# Adafruit_MIDI_FeatherWing.net
KiCad netlist of a schematic drawn in EAGLE
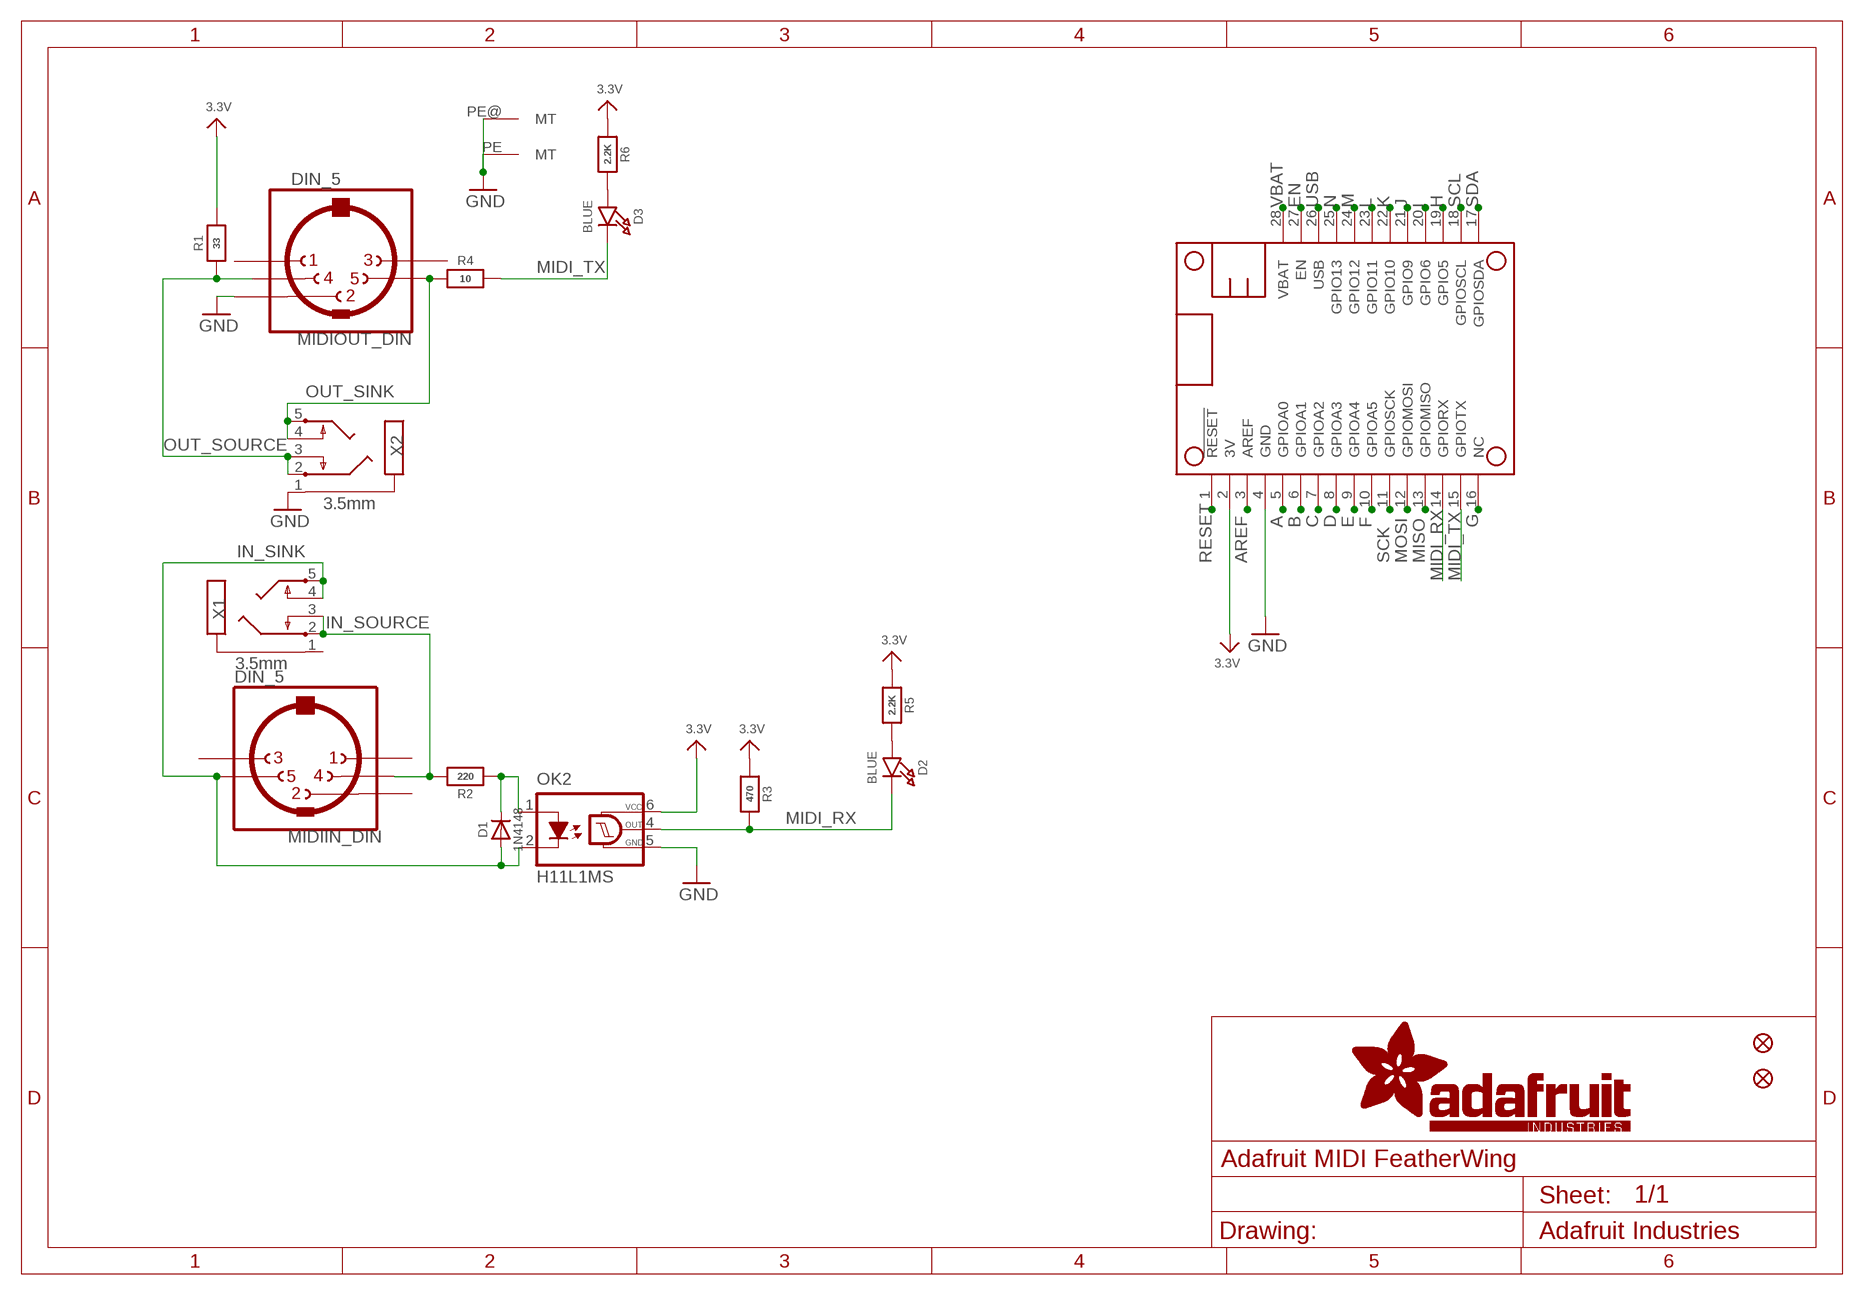
[diagram p0: schematic, sheet 1]

(export (version "E")
  (design (tool "Eeschema 10.0.6"))
  (components
    (comp (ref "D1")
      (value "1N4148")
      (footprint "eagle-import:SOD-323")
      (libsource (lib "eagle-import") (part "DIODESOD-323"))
    )
    (comp (ref "D2")
      (value "BLUE")
      (footprint "eagle-import:CHIPLED_0603")
      (libsource (lib "eagle-import") (part "LED0603"))
    )
    (comp (ref "D3")
      (value "BLUE")
      (footprint "eagle-import:CHIPLED_0603")
      (libsource (lib "eagle-import") (part "LED0603"))
    )
    (comp (ref "FID1")
      (value "FIDUCIAL_1MM")
      (footprint "eagle-import:FIDUCIAL_1MM")
      (libsource (lib "eagle-import") (part "FIDUCIAL_1MM"))
    )
    (comp (ref "FID2")
      (value "FIDUCIAL_1MM")
      (footprint "eagle-import:FIDUCIAL_1MM")
      (libsource (lib "eagle-import") (part "FIDUCIAL_1MM"))
    )
    (comp (ref "MIDIIN")
      (value "DIN_5")
      (footprint "eagle-import:CP-2350")
      (libsource (lib "eagle-import") (part "DIN_5"))
    )
    (comp (ref "MIDIOUT")
      (value "DIN_5")
      (footprint "eagle-import:CP-2350")
      (libsource (lib "eagle-import") (part "DIN_5"))
    )
    (comp (ref "MS1")
      (value "FEATHERWING_NODIM")
      (footprint "eagle-import:FEATHERWING_NODIM")
      (libsource (lib "eagle-import") (part "FEATHERWING_NODIM"))
    )
    (comp (ref "OK2")
      (value "H11L1MS")
      (footprint "eagle-import:DIL6-SMD")
      (libsource (lib "eagle-import") (part "H11LMS1"))
    )
    (comp (ref "R1")
      (value "33")
      (footprint "eagle-import:0603-NO")
      (libsource (lib "eagle-import") (part "RESISTOR_0603_NOOUT"))
    )
    (comp (ref "R2")
      (value "220")
      (footprint "eagle-import:0603-NO")
      (libsource (lib "eagle-import") (part "RESISTOR_0603_NOOUT"))
    )
    (comp (ref "R3")
      (value "470")
      (footprint "eagle-import:0603-NO")
      (libsource (lib "eagle-import") (part "RESISTOR_0603_NOOUT"))
    )
    (comp (ref "R4")
      (value "10")
      (footprint "eagle-import:0603-NO")
      (libsource (lib "eagle-import") (part "RESISTOR_0603_NOOUT"))
    )
    (comp (ref "R5")
      (value "2.2K")
      (footprint "eagle-import:0603-NO")
      (libsource (lib "eagle-import") (part "RESISTOR_0603_NOOUT"))
    )
    (comp (ref "R6")
      (value "2.2K")
      (footprint "eagle-import:0603-NO")
      (libsource (lib "eagle-import") (part "RESISTOR_0603_NOOUT"))
    )
    (comp (ref "X1")
      (value "3.5mm")
      (footprint "eagle-import:STX3100")
      (libsource (lib "eagle-import") (part "AUDIO_STEREOJACK"))
    )
    (comp (ref "X2")
      (value "3.5mm")
      (footprint "eagle-import:STX3100")
      (libsource (lib "eagle-import") (part "AUDIO_STEREOJACK"))
    )
  )
  (nets
    (net (code "1") (name "/A") (class "Default")
      (node (ref "MS1") (pin "5") (pinfunction "GPIOA0_5") (pintype "bidirectional"))
    )
    (net (code "2") (name "/AREF") (class "Default")
      (node (ref "MS1") (pin "3") (pinfunction "AREF_3") (pintype "passive"))
    )
    (net (code "3") (name "/B") (class "Default")
      (node (ref "MS1") (pin "6") (pinfunction "GPIOA1_6") (pintype "bidirectional"))
    )
    (net (code "4") (name "/C") (class "Default")
      (node (ref "MS1") (pin "7") (pinfunction "GPIOA2_7") (pintype "bidirectional"))
    )
    (net (code "5") (name "/D") (class "Default")
      (node (ref "MS1") (pin "8") (pinfunction "GPIOA3_8") (pintype "bidirectional"))
    )
    (net (code "6") (name "/E") (class "Default")
      (node (ref "MS1") (pin "9") (pinfunction "GPIOA4_9") (pintype "bidirectional"))
    )
    (net (code "7") (name "/EN") (class "Default")
      (node (ref "MS1") (pin "27") (pinfunction "EN_27") (pintype "passive"))
    )
    (net (code "8") (name "/F") (class "Default")
      (node (ref "MS1") (pin "10") (pinfunction "GPIOA5_10") (pintype "bidirectional"))
    )
    (net (code "9") (name "/G") (class "Default")
      (node (ref "MS1") (pin "16") (pinfunction "NC_16") (pintype "passive"))
    )
    (net (code "10") (name "/H") (class "Default")
      (node (ref "MS1") (pin "19") (pinfunction "GPIO5_19") (pintype "bidirectional"))
    )
    (net (code "11") (name "/I") (class "Default")
      (node (ref "MS1") (pin "20") (pinfunction "GPIO6_20") (pintype "bidirectional"))
    )
    (net (code "12") (name "/IN_SINK") (class "Default")
      (node (ref "D1") (pin "A") (pinfunction "A_A") (pintype "passive"))
      (node (ref "MIDIIN") (pin "5") (pinfunction "5_5") (pintype "passive"))
      (node (ref "OK2") (pin "2") (pinfunction "C_2") (pintype "passive"))
      (node (ref "X1") (pin "4") (pinfunction "4_4") (pintype "passive"))
      (node (ref "X1") (pin "5") (pinfunction "5_5") (pintype "passive"))
    )
    (net (code "13") (name "/IN_SOURCE") (class "Default")
      (node (ref "MIDIIN") (pin "4") (pinfunction "4_4") (pintype "passive"))
      (node (ref "R2") (pin "2") (pinfunction "2_2") (pintype "passive"))
      (node (ref "X1") (pin "2") (pinfunction "2_2") (pintype "passive"))
      (node (ref "X1") (pin "3") (pinfunction "3_3") (pintype "passive"))
    )
    (net (code "14") (name "/J") (class "Default")
      (node (ref "MS1") (pin "21") (pinfunction "GPIO9_21") (pintype "bidirectional"))
    )
    (net (code "15") (name "/K") (class "Default")
      (node (ref "MS1") (pin "22") (pinfunction "GPIO10_22") (pintype "bidirectional"))
    )
    (net (code "16") (name "/L") (class "Default")
      (node (ref "MS1") (pin "23") (pinfunction "GPIO11_23") (pintype "bidirectional"))
    )
    (net (code "17") (name "/M") (class "Default")
      (node (ref "MS1") (pin "24") (pinfunction "GPIO12_24") (pintype "bidirectional"))
    )
    (net (code "18") (name "/MIDI_RX") (class "Default")
      (node (ref "D2") (pin "C") (pinfunction "C_C") (pintype "passive"))
      (node (ref "MS1") (pin "14") (pinfunction "GPIORX_14") (pintype "bidirectional"))
      (node (ref "OK2") (pin "4") (pinfunction "OUT_4") (pintype "output"))
      (node (ref "R3") (pin "2") (pinfunction "2_2") (pintype "passive"))
    )
    (net (code "19") (name "/MIDI_TX") (class "Default")
      (node (ref "D3") (pin "C") (pinfunction "C_C") (pintype "passive"))
      (node (ref "MS1") (pin "15") (pinfunction "GPIOTX_15") (pintype "bidirectional"))
      (node (ref "R4") (pin "2") (pinfunction "2_2") (pintype "passive"))
    )
    (net (code "20") (name "/MISO") (class "Default")
      (node (ref "MS1") (pin "13") (pinfunction "GPIOMISO_13") (pintype "bidirectional"))
    )
    (net (code "21") (name "/MOSI") (class "Default")
      (node (ref "MS1") (pin "12") (pinfunction "GPIOMOSI_12") (pintype "bidirectional"))
    )
    (net (code "22") (name "/N") (class "Default")
      (node (ref "MS1") (pin "25") (pinfunction "GPIO13_25") (pintype "bidirectional"))
    )
    (net (code "23") (name "/OUT_SINK") (class "Default")
      (node (ref "MIDIOUT") (pin "5") (pinfunction "5_5") (pintype "passive"))
      (node (ref "R4") (pin "1") (pinfunction "1_1") (pintype "passive"))
      (node (ref "X2") (pin "4") (pinfunction "4_4") (pintype "passive"))
      (node (ref "X2") (pin "5") (pinfunction "5_5") (pintype "passive"))
    )
    (net (code "24") (name "/OUT_SOURCE") (class "Default")
      (node (ref "MIDIOUT") (pin "4") (pinfunction "4_4") (pintype "passive"))
      (node (ref "R1") (pin "1") (pinfunction "1_1") (pintype "passive"))
      (node (ref "X2") (pin "2") (pinfunction "2_2") (pintype "passive"))
      (node (ref "X2") (pin "3") (pinfunction "3_3") (pintype "passive"))
    )
    (net (code "25") (name "/RESET") (class "Default")
      (node (ref "MS1") (pin "1") (pinfunction "~{RESET}_1") (pintype "input"))
    )
    (net (code "26") (name "/SCK") (class "Default")
      (node (ref "MS1") (pin "11") (pinfunction "GPIOSCK_11") (pintype "bidirectional"))
    )
    (net (code "27") (name "/SCL") (class "Default")
      (node (ref "MS1") (pin "18") (pinfunction "GPIOSCL_18") (pintype "bidirectional"))
    )
    (net (code "28") (name "/SDA") (class "Default")
      (node (ref "MS1") (pin "17") (pinfunction "GPIOSDA_17") (pintype "bidirectional"))
    )
    (net (code "29") (name "/USB") (class "Default")
      (node (ref "MS1") (pin "26") (pinfunction "USB_26") (pintype "power_in"))
    )
    (net (code "30") (name "/VBAT") (class "Default")
      (node (ref "MS1") (pin "28") (pinfunction "VBAT_28") (pintype "power_in"))
    )
    (net (code "31") (name "3.3V") (class "Default")
      (node (ref "MS1") (pin "2") (pinfunction "3V_2") (pintype "power_in"))
      (node (ref "OK2") (pin "6") (pinfunction "VCC_6") (pintype "power_in"))
      (node (ref "R1") (pin "2") (pinfunction "2_2") (pintype "passive"))
      (node (ref "R3") (pin "1") (pinfunction "1_1") (pintype "passive"))
      (node (ref "R5") (pin "1") (pinfunction "1_1") (pintype "passive"))
      (node (ref "R6") (pin "1") (pinfunction "1_1") (pintype "passive"))
    )
    (net (code "32") (name "GND") (class "Default")
      (node (ref "MIDIOUT") (pin "2") (pinfunction "2_2") (pintype "passive"))
      (node (ref "MIDIOUT") (pin "PE") (pinfunction "MT_PE") (pintype "passive"))
      (node (ref "MIDIOUT") (pin "PE@") (pinfunction "MT_PE@") (pintype "passive"))
      (node (ref "MS1") (pin "4") (pinfunction "GND_4") (pintype "power_in"))
      (node (ref "OK2") (pin "5") (pinfunction "GND_5") (pintype "power_in"))
      (node (ref "X2") (pin "1") (pinfunction "1_1") (pintype "passive"))
    )
    (net (code "33") (name "Net-(D2-PadA)") (class "Default")
      (node (ref "D2") (pin "A") (pinfunction "A_A") (pintype "passive"))
      (node (ref "R5") (pin "2") (pinfunction "2_2") (pintype "passive"))
    )
    (net (code "34") (name "Net-(D3-PadA)") (class "Default")
      (node (ref "D3") (pin "A") (pinfunction "A_A") (pintype "passive"))
      (node (ref "R6") (pin "2") (pinfunction "2_2") (pintype "passive"))
    )
    (net (code "35") (name "Net-(OK2-A)") (class "Default")
      (node (ref "D1") (pin "C") (pinfunction "C_C") (pintype "passive"))
      (node (ref "OK2") (pin "1") (pinfunction "A_1") (pintype "passive"))
      (node (ref "R2") (pin "1") (pinfunction "1_1") (pintype "passive"))
    )
    (net (code "36") (name "unconnected-(MIDIIN-Pad1)") (class "Default")
      (node (ref "MIDIIN") (pin "1") (pinfunction "1_1") (pintype "passive"))
    )
    (net (code "37") (name "unconnected-(MIDIIN-Pad2)") (class "Default")
      (node (ref "MIDIIN") (pin "2") (pinfunction "2_2") (pintype "passive"))
    )
    (net (code "38") (name "unconnected-(MIDIIN-Pad3)") (class "Default")
      (node (ref "MIDIIN") (pin "3") (pinfunction "3_3") (pintype "passive"))
    )
    (net (code "39") (name "unconnected-(MIDIOUT-Pad1)") (class "Default")
      (node (ref "MIDIOUT") (pin "1") (pinfunction "1_1") (pintype "passive"))
    )
    (net (code "40") (name "unconnected-(MIDIOUT-Pad3)") (class "Default")
      (node (ref "MIDIOUT") (pin "3") (pinfunction "3_3") (pintype "passive"))
    )
    (net (code "41") (name "unconnected-(X1-Pad1)") (class "Default")
      (node (ref "X1") (pin "1") (pinfunction "1_1") (pintype "passive"))
    )
  )
)
